# 4_Signals.net
KiCad netlist of a schematic drawn in Altium Designer
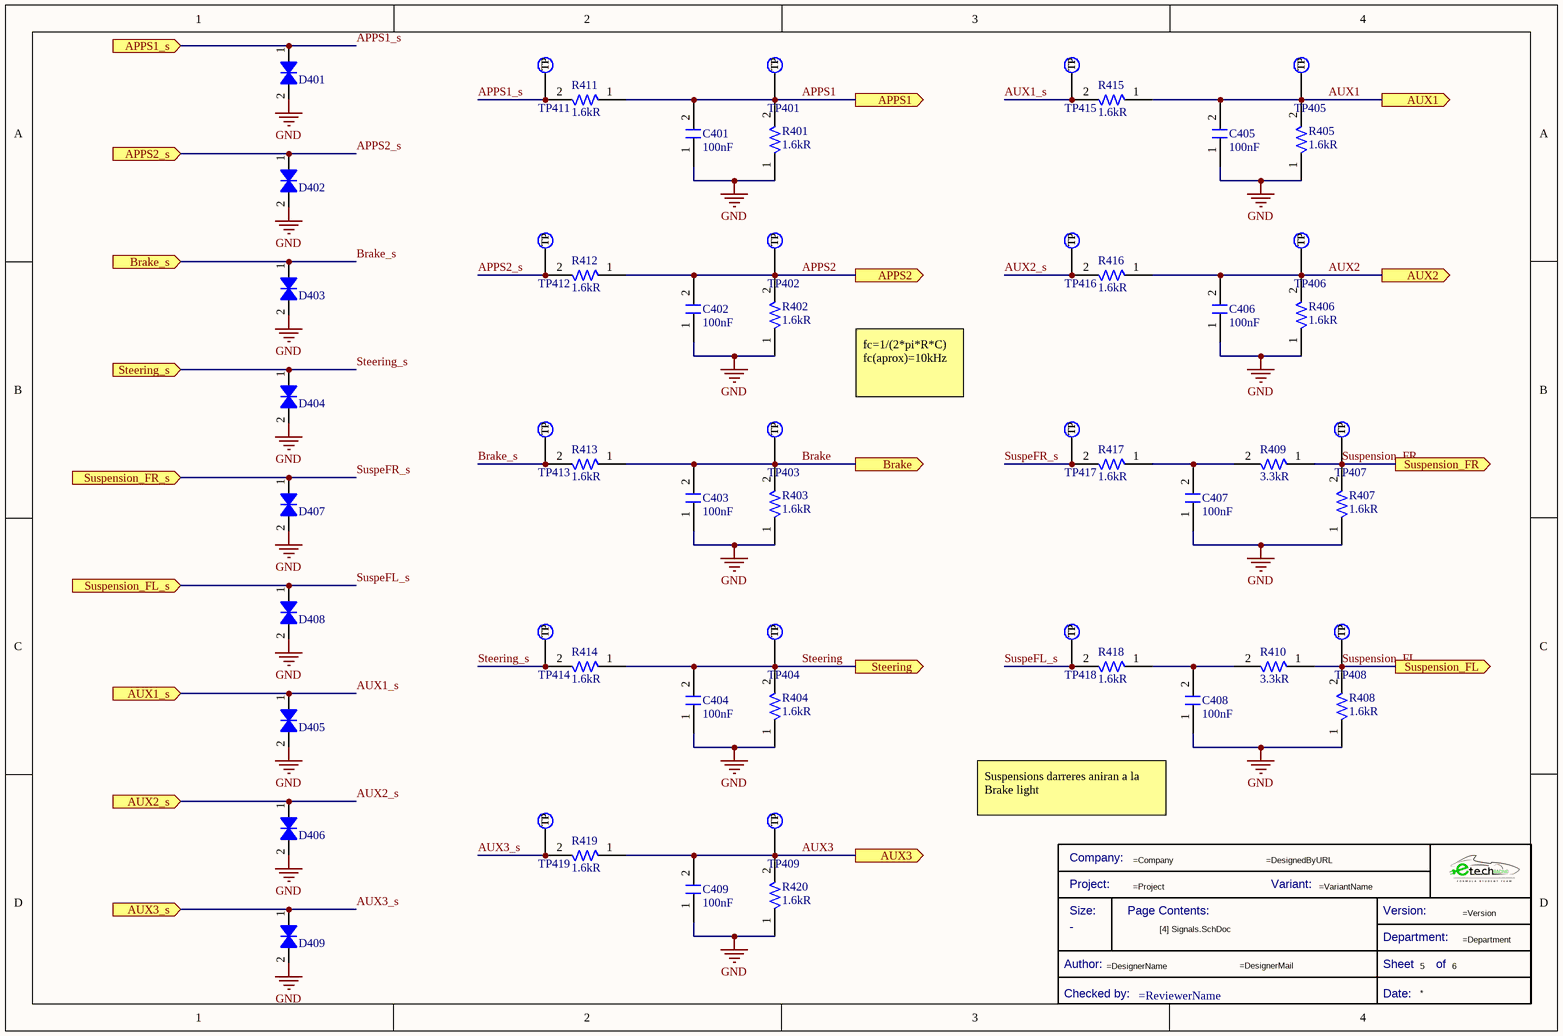
[diagram p0: [4] Signals.SchDoc]

(export (version "E")
  (design (tool "Eeschema 10.0.6"))
  (components
    (comp (ref "C401")
      (value "885012208009")
      (footprint "C1206FNPC-RW")
      (description "Cap, 0.1ΜF, 10V, 10%, X7R, 1206")
      (fields (field (name "TOLERANCE") "10%") (field (name "CAPACITANCE") "100nF"))
      (libsource (lib "Passives") (part "C100n-10V-1206FNPC-X7R"))
    )
    (comp (ref "C402")
      (value "885012208009")
      (footprint "C1206FNPC-RW")
      (description "Cap, 0.1ΜF, 10V, 10%, X7R, 1206")
      (fields (field (name "TOLERANCE") "10%") (field (name "CAPACITANCE") "100nF"))
      (libsource (lib "Passives") (part "C100n-10V-1206FNPC-X7R"))
    )
    (comp (ref "C403")
      (value "885012208009")
      (footprint "C1206FNPC-RW")
      (description "Cap, 0.1ΜF, 10V, 10%, X7R, 1206")
      (fields (field (name "TOLERANCE") "10%") (field (name "CAPACITANCE") "100nF"))
      (libsource (lib "Passives") (part "C100n-10V-1206FNPC-X7R"))
    )
    (comp (ref "C404")
      (value "885012208009")
      (footprint "C1206FNPC-RW")
      (description "Cap, 0.1ΜF, 10V, 10%, X7R, 1206")
      (fields (field (name "TOLERANCE") "10%") (field (name "CAPACITANCE") "100nF"))
      (libsource (lib "Passives") (part "C100n-10V-1206FNPC-X7R"))
    )
    (comp (ref "C405")
      (value "885012208009")
      (footprint "C1206FNPC-RW")
      (description "Cap, 0.1ΜF, 10V, 10%, X7R, 1206")
      (fields (field (name "TOLERANCE") "10%") (field (name "CAPACITANCE") "100nF"))
      (libsource (lib "Passives") (part "C100n-10V-1206FNPC-X7R"))
    )
    (comp (ref "C406")
      (value "885012208009")
      (footprint "C1206FNPC-RW")
      (description "Cap, 0.1ΜF, 10V, 10%, X7R, 1206")
      (fields (field (name "TOLERANCE") "10%") (field (name "CAPACITANCE") "100nF"))
      (libsource (lib "Passives") (part "C100n-10V-1206FNPC-X7R"))
    )
    (comp (ref "C407")
      (value "885012208009")
      (footprint "C1206FNPC-RW")
      (description "Cap, 0.1ΜF, 10V, 10%, X7R, 1206")
      (fields (field (name "TOLERANCE") "10%") (field (name "CAPACITANCE") "100nF"))
      (libsource (lib "Passives") (part "C100n-10V-1206FNPC-X7R"))
    )
    (comp (ref "C408")
      (value "885012208009")
      (footprint "C1206FNPC-RW")
      (description "Cap, 0.1ΜF, 10V, 10%, X7R, 1206")
      (fields (field (name "TOLERANCE") "10%") (field (name "CAPACITANCE") "100nF"))
      (libsource (lib "Passives") (part "C100n-10V-1206FNPC-X7R"))
    )
    (comp (ref "C409")
      (value "885012208009")
      (footprint "C1206FNPC-RW")
      (description "Cap, 0.1ΜF, 10V, 10%, X7R, 1206")
      (fields (field (name "TOLERANCE") "10%") (field (name "CAPACITANCE") "100nF"))
      (libsource (lib "Passives") (part "C100n-10V-1206FNPC-X7R"))
    )
    (comp (ref "D401")
      (value "824501600")
      (footprint "DTVS-DO-214AC")
      (description "TVS diode [Würth Elektronik] 824501600 TVS diode")
      (fields (field (name "MANUFACTURER") "Wurth Electronics"))
      (libsource (lib "Filter components") (part "DTVS-6V-DO-214AC"))
    )
    (comp (ref "D402")
      (value "824501600")
      (footprint "DTVS-DO-214AC")
      (description "TVS diode [Würth Elektronik] 824501600 TVS diode")
      (fields (field (name "MANUFACTURER") "Wurth Electronics"))
      (libsource (lib "Filter components") (part "DTVS-6V-DO-214AC"))
    )
    (comp (ref "D403")
      (value "824501600")
      (footprint "DTVS-DO-214AC")
      (description "TVS diode [Würth Elektronik] 824501600 TVS diode")
      (fields (field (name "MANUFACTURER") "Wurth Electronics"))
      (libsource (lib "Filter components") (part "DTVS-6V-DO-214AC"))
    )
    (comp (ref "D404")
      (value "824501600")
      (footprint "DTVS-DO-214AC")
      (description "TVS diode [Würth Elektronik] 824501600 TVS diode")
      (fields (field (name "MANUFACTURER") "Wurth Electronics"))
      (libsource (lib "Filter components") (part "DTVS-6V-DO-214AC"))
    )
    (comp (ref "D405")
      (value "824501600")
      (footprint "DTVS-DO-214AC")
      (description "TVS diode [Würth Elektronik] 824501600 TVS diode")
      (fields (field (name "MANUFACTURER") "Wurth Electronics"))
      (libsource (lib "Filter components") (part "DTVS-6V-DO-214AC"))
    )
    (comp (ref "D406")
      (value "824501600")
      (footprint "DTVS-DO-214AC")
      (description "TVS diode [Würth Elektronik] 824501600 TVS diode")
      (fields (field (name "MANUFACTURER") "Wurth Electronics"))
      (libsource (lib "Filter components") (part "DTVS-6V-DO-214AC"))
    )
    (comp (ref "D407")
      (value "824501600")
      (footprint "DTVS-DO-214AC")
      (description "TVS diode [Würth Elektronik] 824501600 TVS diode")
      (fields (field (name "MANUFACTURER") "Wurth Electronics"))
      (libsource (lib "Filter components") (part "DTVS-6V-DO-214AC"))
    )
    (comp (ref "D408")
      (value "824501600")
      (footprint "DTVS-DO-214AC")
      (description "TVS diode [Würth Elektronik] 824501600 TVS diode")
      (fields (field (name "MANUFACTURER") "Wurth Electronics"))
      (libsource (lib "Filter components") (part "DTVS-6V-DO-214AC"))
    )
    (comp (ref "D409")
      (value "824501600")
      (footprint "DTVS-DO-214AC")
      (description "TVS diode [Würth Elektronik] 824501600 TVS diode")
      (fields (field (name "MANUFACTURER") "Wurth Electronics"))
      (libsource (lib "Filter components") (part "DTVS-6V-DO-214AC"))
    )
    (comp (ref "R401")
      (value "CRCW12061K60FKEA")
      (footprint "R1206FTK-W")
      (description "Res Thick Film 1206 1.6K Ohm 1% 1/4W ±100ppm/°C Molded SMD SMD Paper T/R")
      (fields (field (name "TOLERANCE") "1%") (field (name "RESISTANCE") "1.6kR"))
      (libsource (lib "Passives") (part "R1.6K-1206FTK"))
    )
    (comp (ref "R402")
      (value "CRCW12061K60FKEA")
      (footprint "R1206FTK-W")
      (description "Res Thick Film 1206 1.6K Ohm 1% 1/4W ±100ppm/°C Molded SMD SMD Paper T/R")
      (fields (field (name "TOLERANCE") "1%") (field (name "RESISTANCE") "1.6kR"))
      (libsource (lib "Passives") (part "R1.6K-1206FTK"))
    )
    (comp (ref "R403")
      (value "CRCW12061K60FKEA")
      (footprint "R1206FTK-W")
      (description "Res Thick Film 1206 1.6K Ohm 1% 1/4W ±100ppm/°C Molded SMD SMD Paper T/R")
      (fields (field (name "TOLERANCE") "1%") (field (name "RESISTANCE") "1.6kR"))
      (libsource (lib "Passives") (part "R1.6K-1206FTK"))
    )
    (comp (ref "R404")
      (value "CRCW12061K60FKEA")
      (footprint "R1206FTK-W")
      (description "Res Thick Film 1206 1.6K Ohm 1% 1/4W ±100ppm/°C Molded SMD SMD Paper T/R")
      (fields (field (name "TOLERANCE") "1%") (field (name "RESISTANCE") "1.6kR"))
      (libsource (lib "Passives") (part "R1.6K-1206FTK"))
    )
    (comp (ref "R405")
      (value "CRCW12061K60FKEA")
      (footprint "R1206FTK-W")
      (description "Res Thick Film 1206 1.6K Ohm 1% 1/4W ±100ppm/°C Molded SMD SMD Paper T/R")
      (fields (field (name "TOLERANCE") "1%") (field (name "RESISTANCE") "1.6kR"))
      (libsource (lib "Passives") (part "R1.6K-1206FTK"))
    )
    (comp (ref "R406")
      (value "CRCW12061K60FKEA")
      (footprint "R1206FTK-W")
      (description "Res Thick Film 1206 1.6K Ohm 1% 1/4W ±100ppm/°C Molded SMD SMD Paper T/R")
      (fields (field (name "TOLERANCE") "1%") (field (name "RESISTANCE") "1.6kR"))
      (libsource (lib "Passives") (part "R1.6K-1206FTK"))
    )
    (comp (ref "R407")
      (value "CRCW12064K30FKEA")
      (footprint "R1206FTK-W")
      (description "Res Thick Film 1206 4.3K Ohm 1% 1/4W ±100ppm/°C Molded SMD SMD Paper T/R")
      (fields (field (name "TOLERANCE") "1%") (field (name "RESISTANCE") "1.6kR"))
      (libsource (lib "Passives") (part "R4.3K-1206FTK"))
    )
    (comp (ref "R408")
      (value "CRCW12064K30FKEA")
      (footprint "R1206FTK-W")
      (description "Res Thick Film 1206 4.3K Ohm 1% 1/4W ±100ppm/°C Molded SMD SMD Paper T/R")
      (fields (field (name "TOLERANCE") "1%") (field (name "RESISTANCE") "1.6kR"))
      (libsource (lib "Passives") (part "R4.3K-1206FTK"))
    )
    (comp (ref "R409")
      (value "CRCW12066K19FKEA")
      (footprint "R1206FTK-W")
      (description "Res Thick Film 1206 6.19K Ohm 1% 1/4W ±100ppm/°C Molded SMD SMD Paper T/R")
      (fields (field (name "TOLERANCE") "1%") (field (name "RESISTANCE") "3.3kR"))
      (libsource (lib "Passives") (part "R6.2K-1206FTK"))
    )
    (comp (ref "R410")
      (value "CRCW12066K19FKEA")
      (footprint "R1206FTK-W")
      (description "Res Thick Film 1206 6.19K Ohm 1% 1/4W ±100ppm/°C Molded SMD SMD Paper T/R")
      (fields (field (name "TOLERANCE") "1%") (field (name "RESISTANCE") "3.3kR"))
      (libsource (lib "Passives") (part "R6.2K-1206FTK"))
    )
    (comp (ref "R411")
      (value "CRCW12061K60FKEA")
      (footprint "R1206FTK-W")
      (description "Res Thick Film 1206 1.6K Ohm 1% 1/4W ±100ppm/°C Molded SMD SMD Paper T/R")
      (fields (field (name "TOLERANCE") "1%") (field (name "RESISTANCE") "1.6kR"))
      (libsource (lib "Passives") (part "R1.6K-1206FTK"))
    )
    (comp (ref "R412")
      (value "CRCW12061K60FKEA")
      (footprint "R1206FTK-W")
      (description "Res Thick Film 1206 1.6K Ohm 1% 1/4W ±100ppm/°C Molded SMD SMD Paper T/R")
      (fields (field (name "TOLERANCE") "1%") (field (name "RESISTANCE") "1.6kR"))
      (libsource (lib "Passives") (part "R1.6K-1206FTK"))
    )
    (comp (ref "R413")
      (value "CRCW12061K60FKEA")
      (footprint "R1206FTK-W")
      (description "Res Thick Film 1206 1.6K Ohm 1% 1/4W ±100ppm/°C Molded SMD SMD Paper T/R")
      (fields (field (name "TOLERANCE") "1%") (field (name "RESISTANCE") "1.6kR"))
      (libsource (lib "Passives") (part "R1.6K-1206FTK"))
    )
    (comp (ref "R414")
      (value "CRCW12061K60FKEA")
      (footprint "R1206FTK-W")
      (description "Res Thick Film 1206 1.6K Ohm 1% 1/4W ±100ppm/°C Molded SMD SMD Paper T/R")
      (fields (field (name "TOLERANCE") "1%") (field (name "RESISTANCE") "1.6kR"))
      (libsource (lib "Passives") (part "R1.6K-1206FTK"))
    )
    (comp (ref "R415")
      (value "CRCW12061K60FKEA")
      (footprint "R1206FTK-W")
      (description "Res Thick Film 1206 1.6K Ohm 1% 1/4W ±100ppm/°C Molded SMD SMD Paper T/R")
      (fields (field (name "TOLERANCE") "1%") (field (name "RESISTANCE") "1.6kR"))
      (libsource (lib "Passives") (part "R1.6K-1206FTK"))
    )
    (comp (ref "R416")
      (value "CRCW12061K60FKEA")
      (footprint "R1206FTK-W")
      (description "Res Thick Film 1206 1.6K Ohm 1% 1/4W ±100ppm/°C Molded SMD SMD Paper T/R")
      (fields (field (name "TOLERANCE") "1%") (field (name "RESISTANCE") "1.6kR"))
      (libsource (lib "Passives") (part "R1.6K-1206FTK"))
    )
    (comp (ref "R417")
      (value "CRCW12061K60FKEA")
      (footprint "R1206FTK-W")
      (description "Res Thick Film 1206 1.6K Ohm 1% 1/4W ±100ppm/°C Molded SMD SMD Paper T/R")
      (fields (field (name "TOLERANCE") "1%") (field (name "RESISTANCE") "1.6kR"))
      (libsource (lib "Passives") (part "R1.6K-1206FTK"))
    )
    (comp (ref "R418")
      (value "CRCW12061K60FKEA")
      (footprint "R1206FTK-W")
      (description "Res Thick Film 1206 1.6K Ohm 1% 1/4W ±100ppm/°C Molded SMD SMD Paper T/R")
      (fields (field (name "TOLERANCE") "1%") (field (name "RESISTANCE") "1.6kR"))
      (libsource (lib "Passives") (part "R1.6K-1206FTK"))
    )
    (comp (ref "R419")
      (value "CRCW12061K60FKEA")
      (footprint "R1206FTK-W")
      (description "Res Thick Film 1206 1.6K Ohm 1% 1/4W ±100ppm/°C Molded SMD SMD Paper T/R")
      (fields (field (name "TOLERANCE") "1%") (field (name "RESISTANCE") "1.6kR"))
      (libsource (lib "Passives") (part "R1.6K-1206FTK"))
    )
    (comp (ref "R420")
      (value "CRCW12061K60FKEA")
      (footprint "R1206FTK-W")
      (description "Res Thick Film 1206 1.6K Ohm 1% 1/4W ±100ppm/°C Molded SMD SMD Paper T/R")
      (fields (field (name "TOLERANCE") "1%") (field (name "RESISTANCE") "1.6kR"))
      (libsource (lib "Passives") (part "R1.6K-1206FTK"))
    )
    (comp (ref "TP401")
      (value "TestPoint")
      (footprint "TestPoint")
      (description "Test Point 1x1 mm")
      (libsource (lib "e-Tech_Racing") (part "TestPoint"))
    )
    (comp (ref "TP402")
      (value "TestPoint")
      (footprint "TestPoint")
      (description "Test Point 1x1 mm")
      (libsource (lib "e-Tech_Racing") (part "TestPoint"))
    )
    (comp (ref "TP403")
      (value "TestPoint")
      (footprint "TestPoint")
      (description "Test Point 1x1 mm")
      (libsource (lib "e-Tech_Racing") (part "TestPoint"))
    )
    (comp (ref "TP404")
      (value "TestPoint")
      (footprint "TestPoint")
      (description "Test Point 1x1 mm")
      (libsource (lib "e-Tech_Racing") (part "TestPoint"))
    )
    (comp (ref "TP405")
      (value "TestPoint")
      (footprint "TestPoint")
      (description "Test Point 1x1 mm")
      (libsource (lib "e-Tech_Racing") (part "TestPoint"))
    )
    (comp (ref "TP406")
      (value "TestPoint")
      (footprint "TestPoint")
      (description "Test Point 1x1 mm")
      (libsource (lib "e-Tech_Racing") (part "TestPoint"))
    )
    (comp (ref "TP407")
      (value "TestPoint")
      (footprint "TestPoint")
      (description "Test Point 1x1 mm")
      (libsource (lib "e-Tech_Racing") (part "TestPoint"))
    )
    (comp (ref "TP408")
      (value "TestPoint")
      (footprint "TestPoint")
      (description "Test Point 1x1 mm")
      (libsource (lib "e-Tech_Racing") (part "TestPoint"))
    )
    (comp (ref "TP409")
      (value "TestPoint")
      (footprint "TestPoint")
      (description "Test Point 1x1 mm")
      (libsource (lib "e-Tech_Racing") (part "TestPoint"))
    )
    (comp (ref "TP411")
      (value "TestPoint")
      (footprint "TestPoint")
      (description "Test Point 1x1 mm")
      (libsource (lib "e-Tech_Racing") (part "TestPoint"))
    )
    (comp (ref "TP412")
      (value "TestPoint")
      (footprint "TestPoint")
      (description "Test Point 1x1 mm")
      (libsource (lib "e-Tech_Racing") (part "TestPoint"))
    )
    (comp (ref "TP413")
      (value "TestPoint")
      (footprint "TestPoint")
      (description "Test Point 1x1 mm")
      (libsource (lib "e-Tech_Racing") (part "TestPoint"))
    )
    (comp (ref "TP414")
      (value "TestPoint")
      (footprint "TestPoint")
      (description "Test Point 1x1 mm")
      (libsource (lib "e-Tech_Racing") (part "TestPoint"))
    )
    (comp (ref "TP415")
      (value "TestPoint")
      (footprint "TestPoint")
      (description "Test Point 1x1 mm")
      (libsource (lib "e-Tech_Racing") (part "TestPoint"))
    )
    (comp (ref "TP416")
      (value "TestPoint")
      (footprint "TestPoint")
      (description "Test Point 1x1 mm")
      (libsource (lib "e-Tech_Racing") (part "TestPoint"))
    )
    (comp (ref "TP417")
      (value "TestPoint")
      (footprint "TestPoint")
      (description "Test Point 1x1 mm")
      (libsource (lib "e-Tech_Racing") (part "TestPoint"))
    )
    (comp (ref "TP418")
      (value "TestPoint")
      (footprint "TestPoint")
      (description "Test Point 1x1 mm")
      (libsource (lib "e-Tech_Racing") (part "TestPoint"))
    )
    (comp (ref "TP419")
      (value "TestPoint")
      (footprint "TestPoint")
      (description "Test Point 1x1 mm")
      (libsource (lib "e-Tech_Racing") (part "TestPoint"))
    )
  )
  (nets
    (net (code "1") (name "/APPS1") (class "Default")
      (node (ref "C401") (pin "2") (pinfunction "2_2") (pintype "passive"))
      (node (ref "R401") (pin "2") (pinfunction "2_2") (pintype "passive"))
      (node (ref "R411") (pin "1") (pinfunction "1_1") (pintype "passive"))
      (node (ref "TP401") (pin "1") (pinfunction "TP_1") (pintype "passive"))
    )
    (net (code "2") (name "/APPS1_s") (class "Default")
      (node (ref "D401") (pin "1") (pinfunction "1_1") (pintype "passive"))
      (node (ref "R411") (pin "2") (pinfunction "2_2") (pintype "passive"))
      (node (ref "TP411") (pin "1") (pinfunction "TP_1") (pintype "passive"))
    )
    (net (code "3") (name "/APPS2") (class "Default")
      (node (ref "C402") (pin "2") (pinfunction "2_2") (pintype "passive"))
      (node (ref "R402") (pin "2") (pinfunction "2_2") (pintype "passive"))
      (node (ref "R412") (pin "1") (pinfunction "1_1") (pintype "passive"))
      (node (ref "TP402") (pin "1") (pinfunction "TP_1") (pintype "passive"))
    )
    (net (code "4") (name "/APPS2_s") (class "Default")
      (node (ref "D402") (pin "1") (pinfunction "1_1") (pintype "passive"))
      (node (ref "R412") (pin "2") (pinfunction "2_2") (pintype "passive"))
      (node (ref "TP412") (pin "1") (pinfunction "TP_1") (pintype "passive"))
    )
    (net (code "5") (name "/AUX1") (class "Default")
      (node (ref "C405") (pin "2") (pinfunction "2_2") (pintype "passive"))
      (node (ref "R405") (pin "2") (pinfunction "2_2") (pintype "passive"))
      (node (ref "R415") (pin "1") (pinfunction "1_1") (pintype "passive"))
      (node (ref "TP405") (pin "1") (pinfunction "TP_1") (pintype "passive"))
    )
    (net (code "6") (name "/AUX1_s") (class "Default")
      (node (ref "D405") (pin "1") (pinfunction "1_1") (pintype "passive"))
      (node (ref "R415") (pin "2") (pinfunction "2_2") (pintype "passive"))
      (node (ref "TP415") (pin "1") (pinfunction "TP_1") (pintype "passive"))
    )
    (net (code "7") (name "/AUX2") (class "Default")
      (node (ref "C406") (pin "2") (pinfunction "2_2") (pintype "passive"))
      (node (ref "R406") (pin "2") (pinfunction "2_2") (pintype "passive"))
      (node (ref "R416") (pin "1") (pinfunction "1_1") (pintype "passive"))
      (node (ref "TP406") (pin "1") (pinfunction "TP_1") (pintype "passive"))
    )
    (net (code "8") (name "/AUX2_s") (class "Default")
      (node (ref "D406") (pin "1") (pinfunction "1_1") (pintype "passive"))
      (node (ref "R416") (pin "2") (pinfunction "2_2") (pintype "passive"))
      (node (ref "TP416") (pin "1") (pinfunction "TP_1") (pintype "passive"))
    )
    (net (code "9") (name "/AUX3") (class "Default")
      (node (ref "C409") (pin "2") (pinfunction "2_2") (pintype "passive"))
      (node (ref "R419") (pin "1") (pinfunction "1_1") (pintype "passive"))
      (node (ref "R420") (pin "2") (pinfunction "2_2") (pintype "passive"))
      (node (ref "TP409") (pin "1") (pinfunction "TP_1") (pintype "passive"))
    )
    (net (code "10") (name "/AUX3_s") (class "Default")
      (node (ref "D409") (pin "1") (pinfunction "1_1") (pintype "passive"))
      (node (ref "R419") (pin "2") (pinfunction "2_2") (pintype "passive"))
      (node (ref "TP419") (pin "1") (pinfunction "TP_1") (pintype "passive"))
    )
    (net (code "11") (name "/Brake") (class "Default")
      (node (ref "C403") (pin "2") (pinfunction "2_2") (pintype "passive"))
      (node (ref "R403") (pin "2") (pinfunction "2_2") (pintype "passive"))
      (node (ref "R413") (pin "1") (pinfunction "1_1") (pintype "passive"))
      (node (ref "TP403") (pin "1") (pinfunction "TP_1") (pintype "passive"))
    )
    (net (code "12") (name "/Brake_s") (class "Default")
      (node (ref "D403") (pin "1") (pinfunction "1_1") (pintype "passive"))
      (node (ref "R413") (pin "2") (pinfunction "2_2") (pintype "passive"))
      (node (ref "TP413") (pin "1") (pinfunction "TP_1") (pintype "passive"))
    )
    (net (code "13") (name "/Steering") (class "Default")
      (node (ref "C404") (pin "2") (pinfunction "2_2") (pintype "passive"))
      (node (ref "R404") (pin "2") (pinfunction "2_2") (pintype "passive"))
      (node (ref "R414") (pin "1") (pinfunction "1_1") (pintype "passive"))
      (node (ref "TP404") (pin "1") (pinfunction "TP_1") (pintype "passive"))
    )
    (net (code "14") (name "/Steering_s") (class "Default")
      (node (ref "D404") (pin "1") (pinfunction "1_1") (pintype "passive"))
      (node (ref "R414") (pin "2") (pinfunction "2_2") (pintype "passive"))
      (node (ref "TP414") (pin "1") (pinfunction "TP_1") (pintype "passive"))
    )
    (net (code "15") (name "/SuspeFL_s") (class "Default")
      (node (ref "D408") (pin "1") (pinfunction "1_1") (pintype "passive"))
      (node (ref "R418") (pin "2") (pinfunction "2_2") (pintype "passive"))
      (node (ref "TP418") (pin "1") (pinfunction "TP_1") (pintype "passive"))
    )
    (net (code "16") (name "/SuspeFR_s") (class "Default")
      (node (ref "D407") (pin "1") (pinfunction "1_1") (pintype "passive"))
      (node (ref "R417") (pin "2") (pinfunction "2_2") (pintype "passive"))
      (node (ref "TP417") (pin "1") (pinfunction "TP_1") (pintype "passive"))
    )
    (net (code "17") (name "/Suspension_FL") (class "Default")
      (node (ref "R408") (pin "2") (pinfunction "2_2") (pintype "passive"))
      (node (ref "R410") (pin "1") (pinfunction "1_1") (pintype "passive"))
      (node (ref "TP408") (pin "1") (pinfunction "TP_1") (pintype "passive"))
    )
    (net (code "18") (name "/Suspension_FR") (class "Default")
      (node (ref "R407") (pin "2") (pinfunction "2_2") (pintype "passive"))
      (node (ref "R409") (pin "1") (pinfunction "1_1") (pintype "passive"))
      (node (ref "TP407") (pin "1") (pinfunction "TP_1") (pintype "passive"))
    )
    (net (code "19") (name "GND") (class "Default")
      (node (ref "C401") (pin "1") (pinfunction "1_1") (pintype "passive"))
      (node (ref "C402") (pin "1") (pinfunction "1_1") (pintype "passive"))
      (node (ref "C403") (pin "1") (pinfunction "1_1") (pintype "passive"))
      (node (ref "C404") (pin "1") (pinfunction "1_1") (pintype "passive"))
      (node (ref "C405") (pin "1") (pinfunction "1_1") (pintype "passive"))
      (node (ref "C406") (pin "1") (pinfunction "1_1") (pintype "passive"))
      (node (ref "C407") (pin "1") (pinfunction "1_1") (pintype "passive"))
      (node (ref "C408") (pin "1") (pinfunction "1_1") (pintype "passive"))
      (node (ref "C409") (pin "1") (pinfunction "1_1") (pintype "passive"))
      (node (ref "D401") (pin "2") (pinfunction "2_2") (pintype "passive"))
      (node (ref "D402") (pin "2") (pinfunction "2_2") (pintype "passive"))
      (node (ref "D403") (pin "2") (pinfunction "2_2") (pintype "passive"))
      (node (ref "D404") (pin "2") (pinfunction "2_2") (pintype "passive"))
      (node (ref "D405") (pin "2") (pinfunction "2_2") (pintype "passive"))
      (node (ref "D406") (pin "2") (pinfunction "2_2") (pintype "passive"))
      (node (ref "D407") (pin "2") (pinfunction "2_2") (pintype "passive"))
      (node (ref "D408") (pin "2") (pinfunction "2_2") (pintype "passive"))
      (node (ref "D409") (pin "2") (pinfunction "2_2") (pintype "passive"))
      (node (ref "R401") (pin "1") (pinfunction "1_1") (pintype "passive"))
      (node (ref "R402") (pin "1") (pinfunction "1_1") (pintype "passive"))
      (node (ref "R403") (pin "1") (pinfunction "1_1") (pintype "passive"))
      (node (ref "R404") (pin "1") (pinfunction "1_1") (pintype "passive"))
      (node (ref "R405") (pin "1") (pinfunction "1_1") (pintype "passive"))
      (node (ref "R406") (pin "1") (pinfunction "1_1") (pintype "passive"))
      (node (ref "R407") (pin "1") (pinfunction "1_1") (pintype "passive"))
      (node (ref "R408") (pin "1") (pinfunction "1_1") (pintype "passive"))
      (node (ref "R420") (pin "1") (pinfunction "1_1") (pintype "passive"))
    )
    (net (code "20") (name "Net-(C407-Pad2)") (class "Default")
      (node (ref "C407") (pin "2") (pinfunction "2_2") (pintype "passive"))
      (node (ref "R409") (pin "2") (pinfunction "2_2") (pintype "passive"))
      (node (ref "R417") (pin "1") (pinfunction "1_1") (pintype "passive"))
    )
    (net (code "21") (name "Net-(C408-Pad2)") (class "Default")
      (node (ref "C408") (pin "2") (pinfunction "2_2") (pintype "passive"))
      (node (ref "R410") (pin "2") (pinfunction "2_2") (pintype "passive"))
      (node (ref "R418") (pin "1") (pinfunction "1_1") (pintype "passive"))
    )
  )
)
